# Apollon_ML_testing.net
KiCad netlist of a schematic drawn in EasyEDA
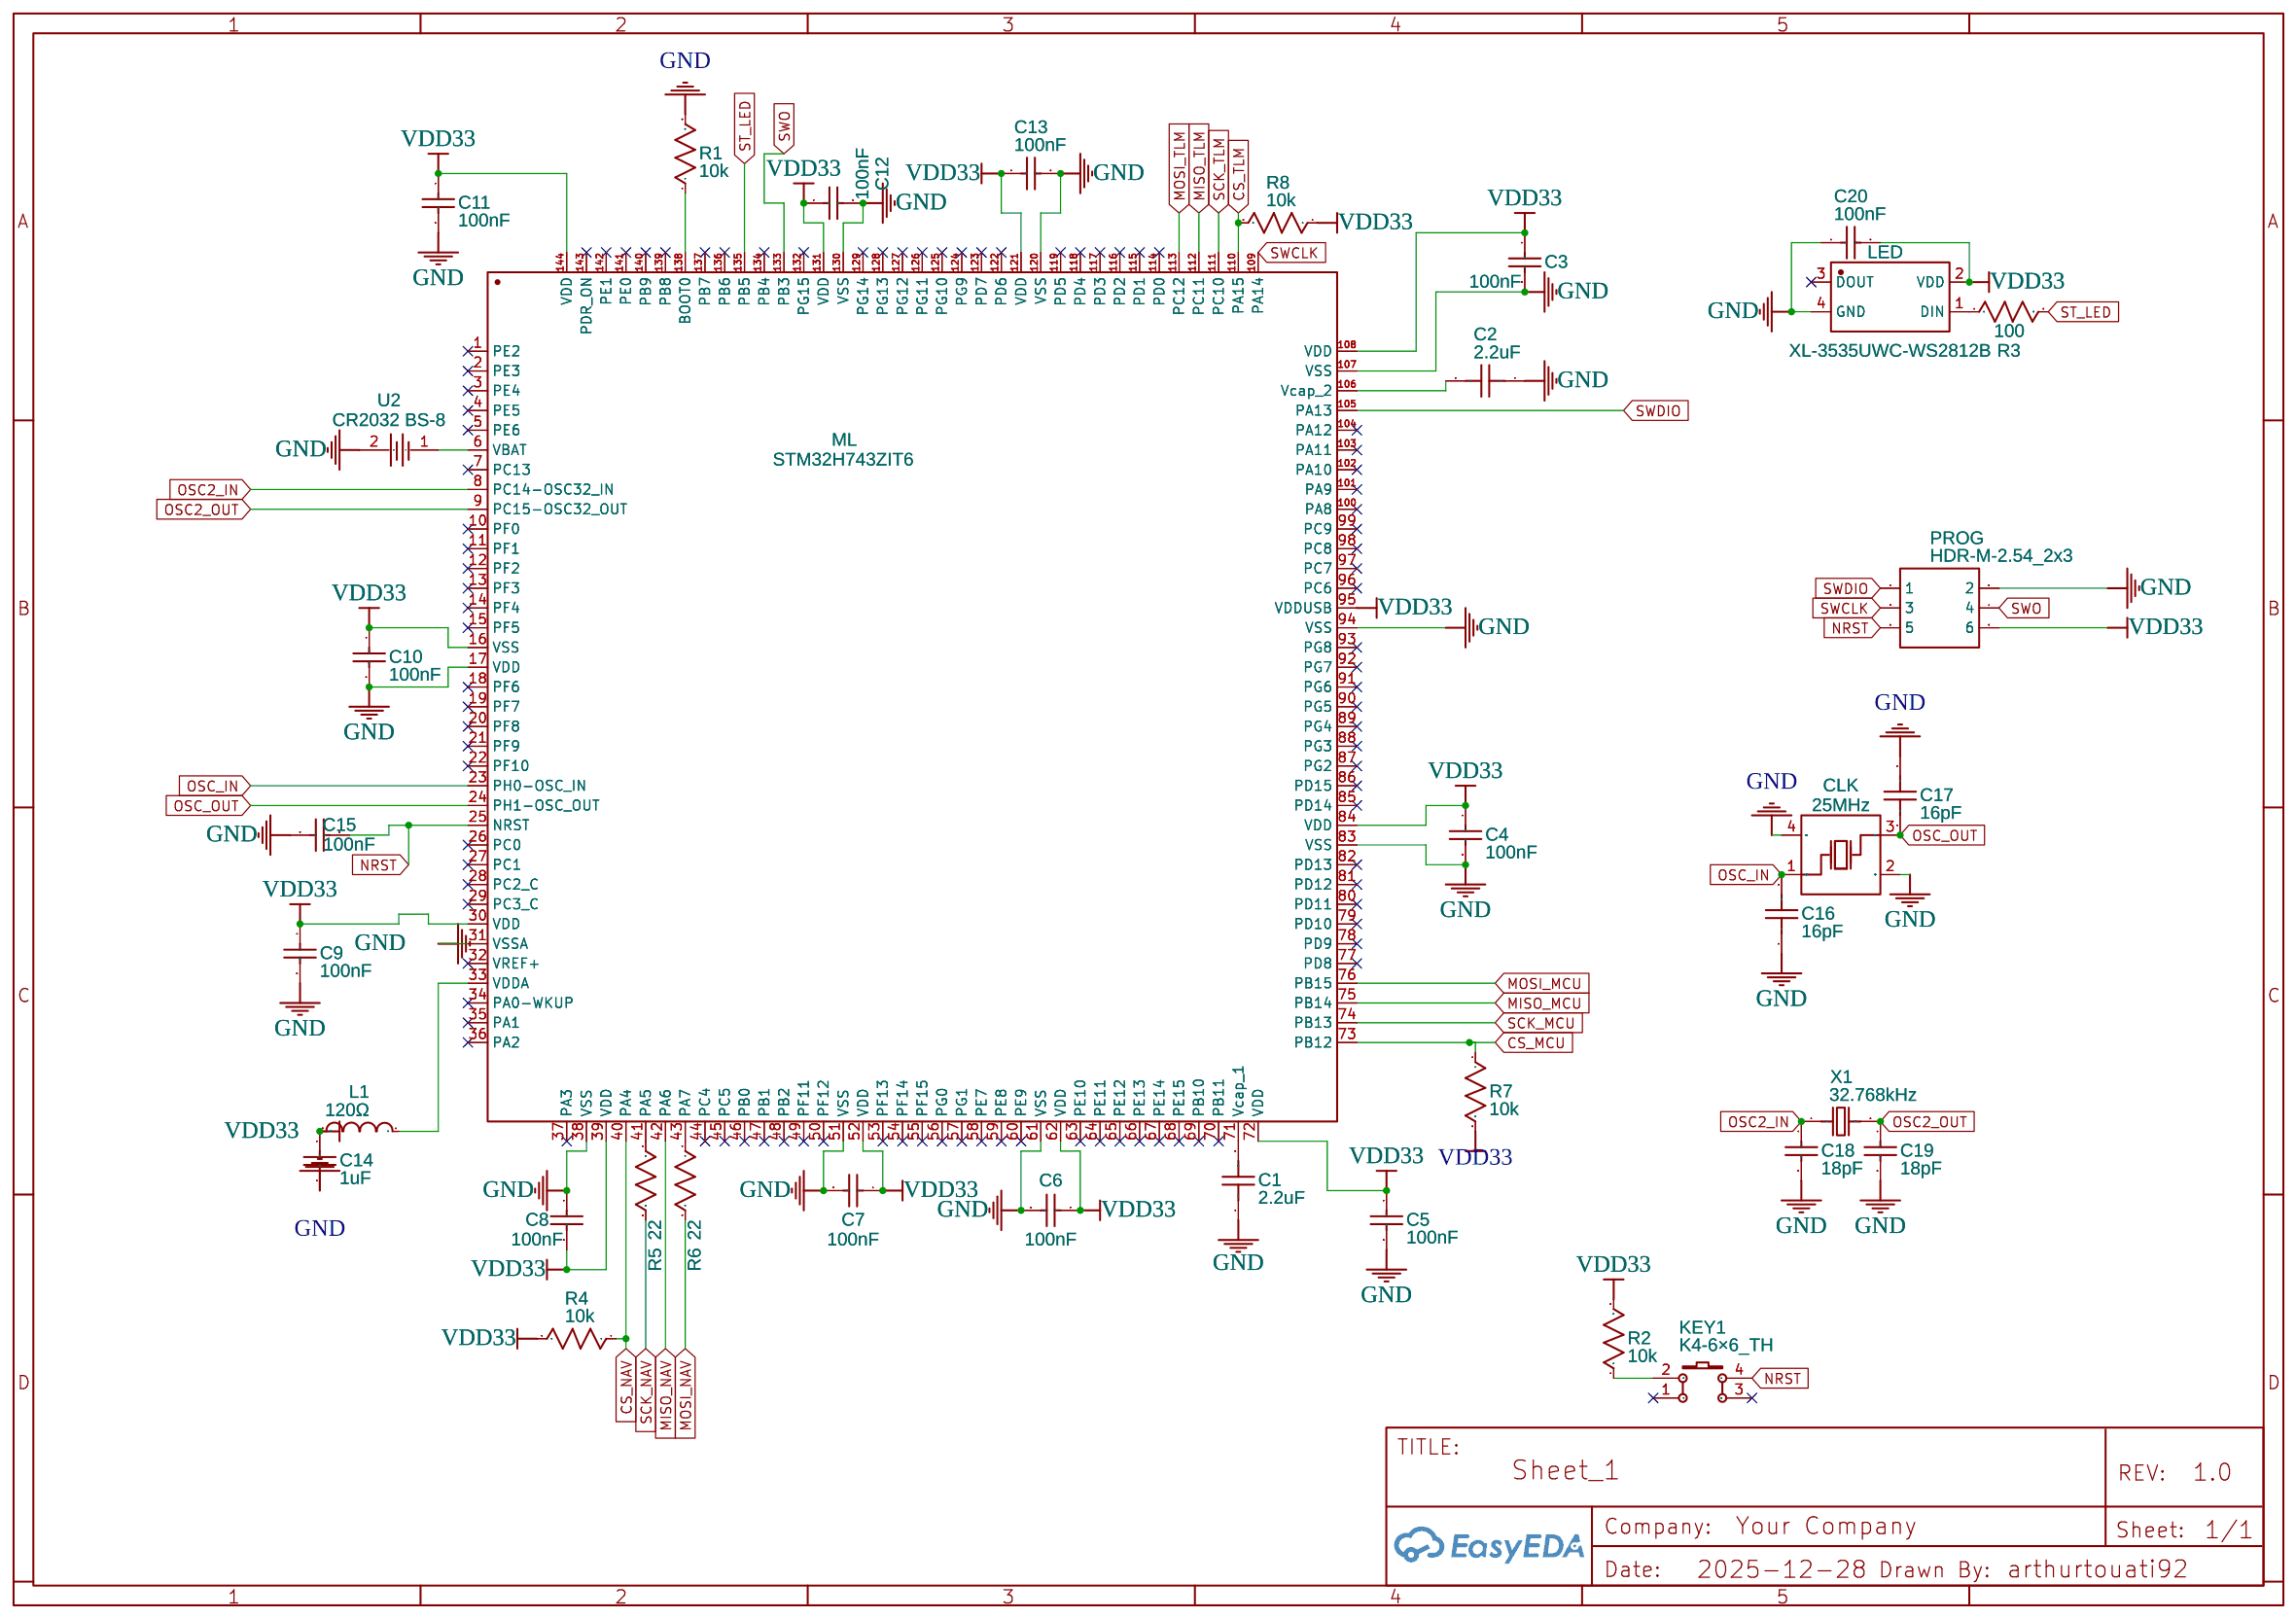
[diagram p0: schematic sheet]

(export (version "E")
  (design (tool "Eeschema 10.0.6"))
  (components
    (comp (ref "C1")
      (value "2.2uF")
      (fields
        (field (name "Manufacturer Part") "CL03A225MP3CRNC")
        (field (name "Manufacturer") "SAMSUNG(三星)")
      )
      (libsource (lib "") (part "CL03A225MP3CRNC_1"))
    )
    (comp (ref "C2")
      (value "2.2uF")
      (fields
        (field (name "Manufacturer Part") "CL03A225MP3CRNC")
        (field (name "Manufacturer") "SAMSUNG(三星)")
      )
      (libsource (lib "") (part "CL03A225MP3CRNC"))
    )
    (comp (ref "C3")
      (value "100nF")
      (fields
        (field (name "Manufacturer Part") "GRM033R61A104KE15D")
        (field (name "Manufacturer") "muRata(村田)")
      )
      (libsource (lib "") (part "GRM033R61A104KE15D"))
    )
    (comp (ref "C4")
      (value "100nF")
      (fields
        (field (name "Manufacturer Part") "GRM033R61A104KE15D")
        (field (name "Manufacturer") "muRata(村田)")
      )
      (libsource (lib "") (part "GRM033R61A104KE15D"))
    )
    (comp (ref "C5")
      (value "100nF")
      (fields
        (field (name "Manufacturer Part") "GRM033R61A104KE15D")
        (field (name "Manufacturer") "muRata(村田)")
      )
      (libsource (lib "") (part "GRM033R61A104KE15D"))
    )
    (comp (ref "C6")
      (value "100nF")
      (fields
        (field (name "Manufacturer Part") "GRM033R61A104KE15D")
        (field (name "Manufacturer") "muRata(村田)")
      )
      (libsource (lib "") (part "GRM033R61A104KE15D_2"))
    )
    (comp (ref "C7")
      (value "100nF")
      (fields
        (field (name "Manufacturer Part") "GRM033R61A104KE15D")
        (field (name "Manufacturer") "muRata(村田)")
      )
      (libsource (lib "") (part "GRM033R61A104KE15D_2"))
    )
    (comp (ref "C8")
      (value "100nF")
      (fields
        (field (name "Manufacturer Part") "GRM033R61A104KE15D")
        (field (name "Manufacturer") "muRata(村田)")
      )
      (libsource (lib "") (part "GRM033R61A104KE15D"))
    )
    (comp (ref "C9")
      (value "100nF")
      (fields
        (field (name "Manufacturer Part") "GRM033R61A104KE15D")
        (field (name "Manufacturer") "muRata(村田)")
      )
      (libsource (lib "") (part "GRM033R61A104KE15D"))
    )
    (comp (ref "C10")
      (value "100nF")
      (fields
        (field (name "Manufacturer Part") "GRM033R61A104KE15D")
        (field (name "Manufacturer") "muRata(村田)")
      )
      (libsource (lib "") (part "GRM033R61A104KE15D"))
    )
    (comp (ref "C11")
      (value "100nF")
      (fields
        (field (name "Manufacturer Part") "GRM033R61A104KE15D")
        (field (name "Manufacturer") "muRata(村田)")
      )
      (libsource (lib "") (part "GRM033R61A104KE15D"))
    )
    (comp (ref "C12")
      (value "100nF")
      (fields
        (field (name "Manufacturer Part") "GRM033R61A104KE15D")
        (field (name "Manufacturer") "muRata(村田)")
      )
      (libsource (lib "") (part "GRM033R61A104KE15D_1"))
    )
    (comp (ref "C13")
      (value "100nF")
      (fields
        (field (name "Manufacturer Part") "GRM033R61A104KE15D")
        (field (name "Manufacturer") "muRata(村田)")
      )
      (libsource (lib "") (part "GRM033R61A104KE15D_1"))
    )
    (comp (ref "C14")
      (value "1uF")
      (fields
        (field (name "Manufacturer Part") "CL03A105MQ3CSNH")
        (field (name "Manufacturer") "SAMSUNG(三星)")
      )
      (libsource (lib "") (part "CL03A105MQ3CSNH"))
    )
    (comp (ref "C15")
      (value "100nF")
      (fields
        (field (name "Manufacturer Part") "GRM033R61A104KE15D")
        (field (name "Manufacturer") "muRata(村田)")
      )
      (libsource (lib "") (part "GRM033R61A104KE15D_2"))
    )
    (comp (ref "C16")
      (value "16pF")
      (fields
        (field (name "Manufacturer Part") "GRM1555C1H160JA01D")
        (field (name "Manufacturer") "muRata(村田)")
      )
      (libsource (lib "") (part "GRM1555C1H160JA01D"))
    )
    (comp (ref "C17")
      (value "16pF")
      (fields
        (field (name "Manufacturer Part") "GRM1555C1H160JA01D")
        (field (name "Manufacturer") "muRata(村田)")
      )
      (libsource (lib "") (part "GRM1555C1H160JA01D"))
    )
    (comp (ref "C18")
      (value "18pF")
      (fields
        (field (name "Manufacturer Part") "GRM033R61A104KE15D")
        (field (name "Manufacturer") "muRata(村田)")
      )
      (libsource (lib "") (part "GRM033R61A104KE15D"))
    )
    (comp (ref "C19")
      (value "18pF")
      (fields
        (field (name "Manufacturer Part") "GRM033R61A104KE15D")
        (field (name "Manufacturer") "muRata(村田)")
      )
      (libsource (lib "") (part "GRM033R61A104KE15D"))
    )
    (comp (ref "C20")
      (value "100nF")
      (fields
        (field (name "Manufacturer Part") "GRM033R61A104KE15D")
        (field (name "Manufacturer") "muRata(村田)")
      )
      (libsource (lib "") (part "GRM033R61A104KE15D_1"))
    )
    (comp (ref "CLK")
      (value "25MHz")
      (fields
        (field (name "Manufacturer Part") "ABM8AIG-25.000MHZ-12-2Z-T3")
        (field (name "Manufacturer") "ABRACON")
      )
      (libsource (lib "") (part "ABM8AIG-25.000MHZ-12-2Z-T3"))
    )
    (comp (ref "KEY1")
      (value "K4-6×6_TH")
      (fields (field (name "Manufacturer Part") "K2-1102DP-E4SW-04") (field (name "Manufacturer") "韩国韩荣"))
      (libsource (lib "") (part "K4-6×6_TH"))
    )
    (comp (ref "L1")
      (value "120Ω")
      (fields (field (name "Manufacturer Part") "BLM03AG121SN1D") (field (name "Manufacturer") "muRata(村田)"))
      (libsource (lib "") (part "BLM03AG121SN1D"))
    )
    (comp (ref "LED")
      (value "XL-3535UWC-WS2812B")
      (fields
        (field (name "Manufacturer Part") "XL-3535UWC-2812B")
        (field (name "Manufacturer") "XINGLIGHT(成兴光)")
      )
      (libsource (lib "") (part "XL-3535UWC-WS2812B"))
    )
    (comp (ref "ML")
      (value "STM32H743ZIT6")
      (fields (field (name "Manufacturer") "ST(意法半导体)"))
      (libsource (lib "") (part "STM32H743ZIT6"))
    )
    (comp (ref "PROG") (value "HDR-M-2.54_2x3") (libsource (lib "") (part "HDR-M-2.54_2x3")))
    (comp (ref "R1") (value "10k") (libsource (lib "") (part "R_0201_US_3")))
    (comp (ref "R2") (value "10k") (libsource (lib "") (part "R_0201_US_3")))
    (comp (ref "R3") (value "100") (libsource (lib "") (part "R_0201_US_1")))
    (comp (ref "R4") (value "10k") (libsource (lib "") (part "R_0201_US_2")))
    (comp (ref "R5") (value "22") (libsource (lib "") (part "R_0201_US")))
    (comp (ref "R6") (value "22") (libsource (lib "") (part "R_0201_US")))
    (comp (ref "R7") (value "10k") (libsource (lib "") (part "R_0201_US")))
    (comp (ref "R8") (value "10k") (libsource (lib "") (part "R_0201_US_2")))
    (comp (ref "U2") (value "CR2032 BS-8") (libsource (lib "") (part "CR2032 BS-8")))
    (comp (ref "X1")
      (value "32.768kHz")
      (fields
        (field (name "Manufacturer Part") "SC-32S32.768kHz20PPM12.5pF")
        (field (name "Manufacturer") "Seiko(精工)")
      )
      (libsource (lib "") (part "SC-32S32.768kHz20PPM12.5pF"))
    )
  )
  (nets
    (net (code "1") (name "CS_MCU") (class "Default")
      (node (ref "ML") (pin "73") (pinfunction "PB12_73") (pintype "unspecified"))
      (node (ref "R7") (pin "1") (pinfunction "1_1") (pintype "unspecified"))
    )
    (net (code "2") (name "CS_NAV") (class "Default")
      (node (ref "ML") (pin "40") (pinfunction "PA4_40") (pintype "unspecified"))
      (node (ref "R4") (pin "1") (pinfunction "1_1") (pintype "unspecified"))
    )
    (net (code "3") (name "CS_TLM") (class "Default")
      (node (ref "ML") (pin "110") (pinfunction "PA15_110") (pintype "unspecified"))
      (node (ref "R8") (pin "2") (pinfunction "2_2") (pintype "unspecified"))
    )
    (net (code "4") (name "GND") (class "Default")
      (node (ref "C1") (pin "1") (pinfunction "1_1") (pintype "unspecified"))
      (node (ref "C10") (pin "2") (pinfunction "2_2") (pintype "input"))
      (node (ref "C11") (pin "2") (pinfunction "2_2") (pintype "input"))
      (node (ref "C12") (pin "2") (pinfunction "2_2") (pintype "input"))
      (node (ref "C13") (pin "2") (pinfunction "2_2") (pintype "input"))
      (node (ref "C14") (pin "2") (pinfunction "2_2") (pintype "input"))
      (node (ref "C15") (pin "2") (pinfunction "2_2") (pintype "input"))
      (node (ref "C16") (pin "1") (pinfunction "1_1") (pintype "unspecified"))
      (node (ref "C17") (pin "2") (pinfunction "2_2") (pintype "unspecified"))
      (node (ref "C18") (pin "2") (pinfunction "2_2") (pintype "input"))
      (node (ref "C19") (pin "2") (pinfunction "2_2") (pintype "input"))
      (node (ref "C2") (pin "1") (pinfunction "1_1") (pintype "unspecified"))
      (node (ref "C20") (pin "1") (pinfunction "1_1") (pintype "input"))
      (node (ref "C3") (pin "2") (pinfunction "2_2") (pintype "input"))
      (node (ref "C4") (pin "2") (pinfunction "2_2") (pintype "input"))
      (node (ref "C5") (pin "2") (pinfunction "2_2") (pintype "input"))
      (node (ref "C6") (pin "2") (pinfunction "2_2") (pintype "input"))
      (node (ref "C7") (pin "2") (pinfunction "2_2") (pintype "input"))
      (node (ref "C8") (pin "1") (pinfunction "1_1") (pintype "input"))
      (node (ref "C9") (pin "2") (pinfunction "2_2") (pintype "input"))
      (node (ref "CLK") (pin "2") (pinfunction "GND_2") (pintype "unspecified"))
      (node (ref "CLK") (pin "4") (pinfunction "GND_4") (pintype "unspecified"))
      (node (ref "LED") (pin "4") (pinfunction "GND_4") (pintype "unspecified"))
      (node (ref "ML") (pin "107") (pinfunction "VSS_107") (pintype "unspecified"))
      (node (ref "ML") (pin "120") (pinfunction "VSS_120") (pintype "unspecified"))
      (node (ref "ML") (pin "130") (pinfunction "VSS_130") (pintype "unspecified"))
      (node (ref "ML") (pin "17") (pinfunction "VDD_17") (pintype "unspecified"))
      (node (ref "ML") (pin "31") (pinfunction "VSSA_31") (pintype "unspecified"))
      (node (ref "ML") (pin "38") (pinfunction "VSS_38") (pintype "unspecified"))
      (node (ref "ML") (pin "51") (pinfunction "VSS_51") (pintype "unspecified"))
      (node (ref "ML") (pin "61") (pinfunction "VSS_61") (pintype "unspecified"))
      (node (ref "ML") (pin "83") (pinfunction "VSS_83") (pintype "unspecified"))
      (node (ref "ML") (pin "94") (pinfunction "VSS_94") (pintype "unspecified"))
      (node (ref "PROG") (pin "2") (pinfunction "2_2") (pintype "input"))
      (node (ref "R1") (pin "2") (pinfunction "2_2") (pintype "unspecified"))
      (node (ref "U2") (pin "2") (pinfunction "+_2") (pintype "input"))
    )
    (net (code "5") (name "MISO_MCU") (class "Default")
      (node (ref "ML") (pin "75") (pinfunction "PB14_75") (pintype "unspecified"))
    )
    (net (code "6") (name "MISO_NAV") (class "Default")
      (node (ref "ML") (pin "42") (pinfunction "PA6_42") (pintype "unspecified"))
    )
    (net (code "7") (name "MISO_TLM") (class "Default")
      (node (ref "ML") (pin "112") (pinfunction "PC11_112") (pintype "unspecified"))
    )
    (net (code "8") (name "MOSI_MCU") (class "Default")
      (node (ref "ML") (pin "76") (pinfunction "PB15_76") (pintype "unspecified"))
    )
    (net (code "9") (name "MOSI_NAV") (class "Default")
      (node (ref "R6") (pin "2") (pinfunction "2_2") (pintype "unspecified"))
    )
    (net (code "10") (name "MOSI_TLM") (class "Default")
      (node (ref "ML") (pin "113") (pinfunction "PC12_113") (pintype "unspecified"))
    )
    (net (code "11") (name "NRST") (class "Default")
      (node (ref "C15") (pin "1") (pinfunction "1_1") (pintype "input"))
      (node (ref "KEY1") (pin "4") (pinfunction "4_4") (pintype "unspecified"))
      (node (ref "ML") (pin "25") (pinfunction "NRST_25") (pintype "unspecified"))
      (node (ref "PROG") (pin "5") (pinfunction "5_5") (pintype "input"))
    )
    (net (code "12") (name "Net-(KEY1-Pad2)") (class "Default")
      (node (ref "KEY1") (pin "2") (pinfunction "2_2") (pintype "unspecified"))
      (node (ref "R2") (pin "1") (pinfunction "1_1") (pintype "unspecified"))
    )
    (net (code "13") (name "Net-(LED-DIN)") (class "Default")
      (node (ref "LED") (pin "1") (pinfunction "DIN_1") (pintype "unspecified"))
      (node (ref "R3") (pin "1") (pinfunction "1_1") (pintype "unspecified"))
    )
    (net (code "14") (name "Net-(ML-BOOT0)") (class "Default")
      (node (ref "ML") (pin "138") (pinfunction "BOOT0_138") (pintype "unspecified"))
      (node (ref "R1") (pin "1") (pinfunction "1_1") (pintype "unspecified"))
    )
    (net (code "15") (name "Net-(ML-PA5)") (class "Default")
      (node (ref "ML") (pin "41") (pinfunction "PA5_41") (pintype "unspecified"))
      (node (ref "R5") (pin "1") (pinfunction "1_1") (pintype "unspecified"))
    )
    (net (code "16") (name "Net-(ML-PA7)") (class "Default")
      (node (ref "ML") (pin "43") (pinfunction "PA7_43") (pintype "unspecified"))
      (node (ref "R6") (pin "1") (pinfunction "1_1") (pintype "unspecified"))
    )
    (net (code "17") (name "Net-(ML-VBAT)") (class "Default")
      (node (ref "ML") (pin "6") (pinfunction "VBAT_6") (pintype "unspecified"))
      (node (ref "U2") (pin "1") (pinfunction "-_1") (pintype "input"))
    )
    (net (code "18") (name "Net-(ML-VDDA)") (class "Default")
      (node (ref "L1") (pin "1") (pinfunction "1_1") (pintype "unspecified"))
      (node (ref "ML") (pin "33") (pinfunction "VDDA_33") (pintype "unspecified"))
    )
    (net (code "19") (name "Net-(ML-Vcap_1)") (class "Default")
      (node (ref "C1") (pin "2") (pinfunction "2_2") (pintype "unspecified"))
      (node (ref "ML") (pin "71") (pinfunction "Vcap_1_71") (pintype "unspecified"))
    )
    (net (code "20") (name "Net-(ML-Vcap_2)") (class "Default")
      (node (ref "C2") (pin "2") (pinfunction "2_2") (pintype "unspecified"))
      (node (ref "ML") (pin "106") (pinfunction "Vcap_2_106") (pintype "unspecified"))
    )
    (net (code "21") (name "OSC2_IN") (class "Default")
      (node (ref "C18") (pin "1") (pinfunction "1_1") (pintype "input"))
      (node (ref "ML") (pin "8") (pinfunction "PC14-OSC32_IN_8") (pintype "unspecified"))
      (node (ref "X1") (pin "1") (pinfunction "1_1") (pintype "unspecified"))
    )
    (net (code "22") (name "OSC2_OUT") (class "Default")
      (node (ref "C19") (pin "1") (pinfunction "1_1") (pintype "input"))
      (node (ref "ML") (pin "9") (pinfunction "PC15-OSC32_OUT_9") (pintype "unspecified"))
      (node (ref "X1") (pin "2") (pinfunction "2_2") (pintype "unspecified"))
    )
    (net (code "23") (name "OSC_IN") (class "Default")
      (node (ref "C16") (pin "2") (pinfunction "2_2") (pintype "unspecified"))
      (node (ref "CLK") (pin "1") (pinfunction "OSC1_1") (pintype "unspecified"))
      (node (ref "ML") (pin "23") (pinfunction "PH0-OSC_IN_23") (pintype "unspecified"))
    )
    (net (code "24") (name "OSC_OUT") (class "Default")
      (node (ref "C17") (pin "1") (pinfunction "1_1") (pintype "unspecified"))
      (node (ref "CLK") (pin "3") (pinfunction "OSC2_3") (pintype "unspecified"))
      (node (ref "ML") (pin "24") (pinfunction "PH1-OSC_OUT_24") (pintype "unspecified"))
    )
    (net (code "25") (name "SCK_MCU") (class "Default")
      (node (ref "ML") (pin "74") (pinfunction "PB13_74") (pintype "unspecified"))
    )
    (net (code "26") (name "SCK_NAV") (class "Default")
      (node (ref "R5") (pin "2") (pinfunction "2_2") (pintype "unspecified"))
    )
    (net (code "27") (name "SCK_TLM") (class "Default")
      (node (ref "ML") (pin "111") (pinfunction "PC10_111") (pintype "unspecified"))
    )
    (net (code "28") (name "ST_LED") (class "Default")
      (node (ref "ML") (pin "135") (pinfunction "PB5_135") (pintype "unspecified"))
      (node (ref "R3") (pin "2") (pinfunction "2_2") (pintype "unspecified"))
    )
    (net (code "29") (name "SWCLK") (class "Default")
      (node (ref "ML") (pin "109") (pinfunction "PA14_109") (pintype "unspecified"))
      (node (ref "PROG") (pin "3") (pinfunction "3_3") (pintype "input"))
    )
    (net (code "30") (name "SWDIO") (class "Default")
      (node (ref "ML") (pin "105") (pinfunction "PA13_105") (pintype "unspecified"))
      (node (ref "PROG") (pin "1") (pinfunction "1_1") (pintype "input"))
    )
    (net (code "31") (name "SWO") (class "Default")
      (node (ref "ML") (pin "133") (pinfunction "PB3_133") (pintype "unspecified"))
      (node (ref "PROG") (pin "4") (pinfunction "4_4") (pintype "input"))
    )
    (net (code "32") (name "VDD33") (class "Default")
      (node (ref "C10") (pin "1") (pinfunction "1_1") (pintype "input"))
      (node (ref "C11") (pin "1") (pinfunction "1_1") (pintype "input"))
      (node (ref "C12") (pin "1") (pinfunction "1_1") (pintype "input"))
      (node (ref "C13") (pin "1") (pinfunction "1_1") (pintype "input"))
      (node (ref "C14") (pin "1") (pinfunction "1_1") (pintype "input"))
      (node (ref "C20") (pin "2") (pinfunction "2_2") (pintype "input"))
      (node (ref "C3") (pin "1") (pinfunction "1_1") (pintype "input"))
      (node (ref "C4") (pin "1") (pinfunction "1_1") (pintype "input"))
      (node (ref "C5") (pin "1") (pinfunction "1_1") (pintype "input"))
      (node (ref "C6") (pin "1") (pinfunction "1_1") (pintype "input"))
      (node (ref "C7") (pin "1") (pinfunction "1_1") (pintype "input"))
      (node (ref "C8") (pin "2") (pinfunction "2_2") (pintype "input"))
      (node (ref "C9") (pin "1") (pinfunction "1_1") (pintype "input"))
      (node (ref "L1") (pin "2") (pinfunction "2_2") (pintype "unspecified"))
      (node (ref "LED") (pin "2") (pinfunction "VDD_2") (pintype "unspecified"))
      (node (ref "ML") (pin "108") (pinfunction "VDD_108") (pintype "unspecified"))
      (node (ref "ML") (pin "121") (pinfunction "VDD_121") (pintype "unspecified"))
      (node (ref "ML") (pin "131") (pinfunction "VDD_131") (pintype "unspecified"))
      (node (ref "ML") (pin "144") (pinfunction "VDD_144") (pintype "unspecified"))
      (node (ref "ML") (pin "16") (pinfunction "VSS_16") (pintype "unspecified"))
      (node (ref "ML") (pin "30") (pinfunction "VDD_30") (pintype "unspecified"))
      (node (ref "ML") (pin "39") (pinfunction "VDD_39") (pintype "unspecified"))
      (node (ref "ML") (pin "52") (pinfunction "VDD_52") (pintype "unspecified"))
      (node (ref "ML") (pin "62") (pinfunction "VDD_62") (pintype "unspecified"))
      (node (ref "ML") (pin "72") (pinfunction "VDD_72") (pintype "unspecified"))
      (node (ref "ML") (pin "84") (pinfunction "VDD_84") (pintype "unspecified"))
      (node (ref "ML") (pin "95") (pinfunction "VDDUSB_95") (pintype "unspecified"))
      (node (ref "PROG") (pin "6") (pinfunction "6_6") (pintype "input"))
      (node (ref "R2") (pin "2") (pinfunction "2_2") (pintype "unspecified"))
      (node (ref "R4") (pin "2") (pinfunction "2_2") (pintype "unspecified"))
      (node (ref "R7") (pin "2") (pinfunction "2_2") (pintype "unspecified"))
      (node (ref "R8") (pin "1") (pinfunction "1_1") (pintype "unspecified"))
    )
    (net (code "33") (name "unconnected-(KEY1-Pad1)") (class "Default")
      (node (ref "KEY1") (pin "1") (pinfunction "1_1") (pintype "unspecified+no_connect"))
    )
    (net (code "34") (name "unconnected-(KEY1-Pad3)") (class "Default")
      (node (ref "KEY1") (pin "3") (pinfunction "3_3") (pintype "unspecified+no_connect"))
    )
    (net (code "35") (name "unconnected-(LED-DOUT-Pad3)") (class "Default")
      (node (ref "LED") (pin "3") (pinfunction "DOUT_3") (pintype "unspecified+no_connect"))
    )
    (net (code "36") (name "unconnected-(ML-PA0-WKUP-Pad34)") (class "Default")
      (node (ref "ML") (pin "34") (pinfunction "PA0-WKUP_34") (pintype "unspecified+no_connect"))
    )
    (net (code "37") (name "unconnected-(ML-PA1-Pad35)") (class "Default")
      (node (ref "ML") (pin "35") (pinfunction "PA1_35") (pintype "unspecified+no_connect"))
    )
    (net (code "38") (name "unconnected-(ML-PA2-Pad36)") (class "Default")
      (node (ref "ML") (pin "36") (pinfunction "PA2_36") (pintype "unspecified+no_connect"))
    )
    (net (code "39") (name "unconnected-(ML-PA3-Pad37)") (class "Default")
      (node (ref "ML") (pin "37") (pinfunction "PA3_37") (pintype "unspecified+no_connect"))
    )
    (net (code "40") (name "unconnected-(ML-PA8-Pad100)") (class "Default")
      (node (ref "ML") (pin "100") (pinfunction "PA8_100") (pintype "unspecified+no_connect"))
    )
    (net (code "41") (name "unconnected-(ML-PA9-Pad101)") (class "Default")
      (node (ref "ML") (pin "101") (pinfunction "PA9_101") (pintype "unspecified+no_connect"))
    )
    (net (code "42") (name "unconnected-(ML-PA10-Pad102)") (class "Default")
      (node (ref "ML") (pin "102") (pinfunction "PA10_102") (pintype "unspecified+no_connect"))
    )
    (net (code "43") (name "unconnected-(ML-PA11-Pad103)") (class "Default")
      (node (ref "ML") (pin "103") (pinfunction "PA11_103") (pintype "unspecified+no_connect"))
    )
    (net (code "44") (name "unconnected-(ML-PA12-Pad104)") (class "Default")
      (node (ref "ML") (pin "104") (pinfunction "PA12_104") (pintype "unspecified+no_connect"))
    )
    (net (code "45") (name "unconnected-(ML-PB0-Pad46)") (class "Default")
      (node (ref "ML") (pin "46") (pinfunction "PB0_46") (pintype "unspecified+no_connect"))
    )
    (net (code "46") (name "unconnected-(ML-PB1-Pad47)") (class "Default")
      (node (ref "ML") (pin "47") (pinfunction "PB1_47") (pintype "unspecified+no_connect"))
    )
    (net (code "47") (name "unconnected-(ML-PB2-Pad48)") (class "Default")
      (node (ref "ML") (pin "48") (pinfunction "PB2_48") (pintype "unspecified+no_connect"))
    )
    (net (code "48") (name "unconnected-(ML-PB4-Pad134)") (class "Default")
      (node (ref "ML") (pin "134") (pinfunction "PB4_134") (pintype "unspecified+no_connect"))
    )
    (net (code "49") (name "unconnected-(ML-PB6-Pad136)") (class "Default")
      (node (ref "ML") (pin "136") (pinfunction "PB6_136") (pintype "unspecified+no_connect"))
    )
    (net (code "50") (name "unconnected-(ML-PB7-Pad137)") (class "Default")
      (node (ref "ML") (pin "137") (pinfunction "PB7_137") (pintype "unspecified+no_connect"))
    )
    (net (code "51") (name "unconnected-(ML-PB8-Pad139)") (class "Default")
      (node (ref "ML") (pin "139") (pinfunction "PB8_139") (pintype "unspecified+no_connect"))
    )
    (net (code "52") (name "unconnected-(ML-PB9-Pad140)") (class "Default")
      (node (ref "ML") (pin "140") (pinfunction "PB9_140") (pintype "unspecified+no_connect"))
    )
    (net (code "53") (name "unconnected-(ML-PB10-Pad69)") (class "Default")
      (node (ref "ML") (pin "69") (pinfunction "PB10_69") (pintype "unspecified+no_connect"))
    )
    (net (code "54") (name "unconnected-(ML-PB11-Pad70)") (class "Default")
      (node (ref "ML") (pin "70") (pinfunction "PB11_70") (pintype "unspecified+no_connect"))
    )
    (net (code "55") (name "unconnected-(ML-PC0-Pad26)") (class "Default")
      (node (ref "ML") (pin "26") (pinfunction "PC0_26") (pintype "unspecified+no_connect"))
    )
    (net (code "56") (name "unconnected-(ML-PC1-Pad27)") (class "Default")
      (node (ref "ML") (pin "27") (pinfunction "PC1_27") (pintype "unspecified+no_connect"))
    )
    (net (code "57") (name "unconnected-(ML-PC2_C-Pad28)") (class "Default")
      (node (ref "ML") (pin "28") (pinfunction "PC2_C_28") (pintype "unspecified+no_connect"))
    )
    (net (code "58") (name "unconnected-(ML-PC3_C-Pad29)") (class "Default")
      (node (ref "ML") (pin "29") (pinfunction "PC3_C_29") (pintype "unspecified+no_connect"))
    )
    (net (code "59") (name "unconnected-(ML-PC4-Pad44)") (class "Default")
      (node (ref "ML") (pin "44") (pinfunction "PC4_44") (pintype "unspecified+no_connect"))
    )
    (net (code "60") (name "unconnected-(ML-PC5-Pad45)") (class "Default")
      (node (ref "ML") (pin "45") (pinfunction "PC5_45") (pintype "unspecified+no_connect"))
    )
    (net (code "61") (name "unconnected-(ML-PC6-Pad96)") (class "Default")
      (node (ref "ML") (pin "96") (pinfunction "PC6_96") (pintype "unspecified+no_connect"))
    )
    (net (code "62") (name "unconnected-(ML-PC7-Pad97)") (class "Default")
      (node (ref "ML") (pin "97") (pinfunction "PC7_97") (pintype "unspecified+no_connect"))
    )
    (net (code "63") (name "unconnected-(ML-PC8-Pad98)") (class "Default")
      (node (ref "ML") (pin "98") (pinfunction "PC8_98") (pintype "unspecified+no_connect"))
    )
    (net (code "64") (name "unconnected-(ML-PC9-Pad99)") (class "Default")
      (node (ref "ML") (pin "99") (pinfunction "PC9_99") (pintype "unspecified+no_connect"))
    )
    (net (code "65") (name "unconnected-(ML-PC13-Pad7)") (class "Default")
      (node (ref "ML") (pin "7") (pinfunction "PC13_7") (pintype "unspecified+no_connect"))
    )
    (net (code "66") (name "unconnected-(ML-PD0-Pad114)") (class "Default")
      (node (ref "ML") (pin "114") (pinfunction "PD0_114") (pintype "unspecified+no_connect"))
    )
    (net (code "67") (name "unconnected-(ML-PD1-Pad115)") (class "Default")
      (node (ref "ML") (pin "115") (pinfunction "PD1_115") (pintype "unspecified+no_connect"))
    )
    (net (code "68") (name "unconnected-(ML-PD2-Pad116)") (class "Default")
      (node (ref "ML") (pin "116") (pinfunction "PD2_116") (pintype "unspecified+no_connect"))
    )
    (net (code "69") (name "unconnected-(ML-PD3-Pad117)") (class "Default")
      (node (ref "ML") (pin "117") (pinfunction "PD3_117") (pintype "unspecified+no_connect"))
    )
    (net (code "70") (name "unconnected-(ML-PD4-Pad118)") (class "Default")
      (node (ref "ML") (pin "118") (pinfunction "PD4_118") (pintype "unspecified+no_connect"))
    )
    (net (code "71") (name "unconnected-(ML-PD5-Pad119)") (class "Default")
      (node (ref "ML") (pin "119") (pinfunction "PD5_119") (pintype "unspecified+no_connect"))
    )
    (net (code "72") (name "unconnected-(ML-PD6-Pad122)") (class "Default")
      (node (ref "ML") (pin "122") (pinfunction "PD6_122") (pintype "unspecified+no_connect"))
    )
    (net (code "73") (name "unconnected-(ML-PD7-Pad123)") (class "Default")
      (node (ref "ML") (pin "123") (pinfunction "PD7_123") (pintype "unspecified+no_connect"))
    )
    (net (code "74") (name "unconnected-(ML-PD8-Pad77)") (class "Default")
      (node (ref "ML") (pin "77") (pinfunction "PD8_77") (pintype "unspecified+no_connect"))
    )
    (net (code "75") (name "unconnected-(ML-PD9-Pad78)") (class "Default")
      (node (ref "ML") (pin "78") (pinfunction "PD9_78") (pintype "unspecified+no_connect"))
    )
    (net (code "76") (name "unconnected-(ML-PD10-Pad79)") (class "Default")
      (node (ref "ML") (pin "79") (pinfunction "PD10_79") (pintype "unspecified+no_connect"))
    )
    (net (code "77") (name "unconnected-(ML-PD11-Pad80)") (class "Default")
      (node (ref "ML") (pin "80") (pinfunction "PD11_80") (pintype "unspecified+no_connect"))
    )
    (net (code "78") (name "unconnected-(ML-PD12-Pad81)") (class "Default")
      (node (ref "ML") (pin "81") (pinfunction "PD12_81") (pintype "unspecified+no_connect"))
    )
    (net (code "79") (name "unconnected-(ML-PD13-Pad82)") (class "Default")
      (node (ref "ML") (pin "82") (pinfunction "PD13_82") (pintype "unspecified+no_connect"))
    )
    (net (code "80") (name "unconnected-(ML-PD14-Pad85)") (class "Default")
      (node (ref "ML") (pin "85") (pinfunction "PD14_85") (pintype "unspecified+no_connect"))
    )
    (net (code "81") (name "unconnected-(ML-PD15-Pad86)") (class "Default")
      (node (ref "ML") (pin "86") (pinfunction "PD15_86") (pintype "unspecified+no_connect"))
    )
    (net (code "82") (name "unconnected-(ML-PDR_ON-Pad143)") (class "Default")
      (node (ref "ML") (pin "143") (pinfunction "PDR_ON_143") (pintype "unspecified+no_connect"))
    )
    (net (code "83") (name "unconnected-(ML-PE0-Pad141)") (class "Default")
      (node (ref "ML") (pin "141") (pinfunction "PE0_141") (pintype "unspecified+no_connect"))
    )
    (net (code "84") (name "unconnected-(ML-PE1-Pad142)") (class "Default")
      (node (ref "ML") (pin "142") (pinfunction "PE1_142") (pintype "unspecified+no_connect"))
    )
    (net (code "85") (name "unconnected-(ML-PE2-Pad1)") (class "Default")
      (node (ref "ML") (pin "1") (pinfunction "PE2_1") (pintype "unspecified+no_connect"))
    )
    (net (code "86") (name "unconnected-(ML-PE3-Pad2)") (class "Default")
      (node (ref "ML") (pin "2") (pinfunction "PE3_2") (pintype "unspecified+no_connect"))
    )
    (net (code "87") (name "unconnected-(ML-PE4-Pad3)") (class "Default")
      (node (ref "ML") (pin "3") (pinfunction "PE4_3") (pintype "unspecified+no_connect"))
    )
    (net (code "88") (name "unconnected-(ML-PE5-Pad4)") (class "Default")
      (node (ref "ML") (pin "4") (pinfunction "PE5_4") (pintype "unspecified+no_connect"))
    )
    (net (code "89") (name "unconnected-(ML-PE6-Pad5)") (class "Default")
      (node (ref "ML") (pin "5") (pinfunction "PE6_5") (pintype "unspecified+no_connect"))
    )
    (net (code "90") (name "unconnected-(ML-PE7-Pad58)") (class "Default")
      (node (ref "ML") (pin "58") (pinfunction "PE7_58") (pintype "unspecified+no_connect"))
    )
    (net (code "91") (name "unconnected-(ML-PE8-Pad59)") (class "Default")
      (node (ref "ML") (pin "59") (pinfunction "PE8_59") (pintype "unspecified+no_connect"))
    )
    (net (code "92") (name "unconnected-(ML-PE9-Pad60)") (class "Default")
      (node (ref "ML") (pin "60") (pinfunction "PE9_60") (pintype "unspecified+no_connect"))
    )
    (net (code "93") (name "unconnected-(ML-PE10-Pad63)") (class "Default")
      (node (ref "ML") (pin "63") (pinfunction "PE10_63") (pintype "unspecified+no_connect"))
    )
    (net (code "94") (name "unconnected-(ML-PE11-Pad64)") (class "Default")
      (node (ref "ML") (pin "64") (pinfunction "PE11_64") (pintype "unspecified+no_connect"))
    )
    (net (code "95") (name "unconnected-(ML-PE12-Pad65)") (class "Default")
      (node (ref "ML") (pin "65") (pinfunction "PE12_65") (pintype "unspecified+no_connect"))
    )
    (net (code "96") (name "unconnected-(ML-PE13-Pad66)") (class "Default")
      (node (ref "ML") (pin "66") (pinfunction "PE13_66") (pintype "unspecified+no_connect"))
    )
    (net (code "97") (name "unconnected-(ML-PE14-Pad67)") (class "Default")
      (node (ref "ML") (pin "67") (pinfunction "PE14_67") (pintype "unspecified+no_connect"))
    )
    (net (code "98") (name "unconnected-(ML-PE15-Pad68)") (class "Default")
      (node (ref "ML") (pin "68") (pinfunction "PE15_68") (pintype "unspecified+no_connect"))
    )
    (net (code "99") (name "unconnected-(ML-PF0-Pad10)") (class "Default")
      (node (ref "ML") (pin "10") (pinfunction "PF0_10") (pintype "unspecified+no_connect"))
    )
    (net (code "100") (name "unconnected-(ML-PF1-Pad11)") (class "Default")
      (node (ref "ML") (pin "11") (pinfunction "PF1_11") (pintype "unspecified+no_connect"))
    )
    (net (code "101") (name "unconnected-(ML-PF2-Pad12)") (class "Default")
      (node (ref "ML") (pin "12") (pinfunction "PF2_12") (pintype "unspecified+no_connect"))
    )
    (net (code "102") (name "unconnected-(ML-PF3-Pad13)") (class "Default")
      (node (ref "ML") (pin "13") (pinfunction "PF3_13") (pintype "unspecified+no_connect"))
    )
    (net (code "103") (name "unconnected-(ML-PF4-Pad14)") (class "Default")
      (node (ref "ML") (pin "14") (pinfunction "PF4_14") (pintype "unspecified+no_connect"))
    )
    (net (code "104") (name "unconnected-(ML-PF5-Pad15)") (class "Default")
      (node (ref "ML") (pin "15") (pinfunction "PF5_15") (pintype "unspecified+no_connect"))
    )
    (net (code "105") (name "unconnected-(ML-PF6-Pad18)") (class "Default")
      (node (ref "ML") (pin "18") (pinfunction "PF6_18") (pintype "unspecified+no_connect"))
    )
    (net (code "106") (name "unconnected-(ML-PF7-Pad19)") (class "Default")
      (node (ref "ML") (pin "19") (pinfunction "PF7_19") (pintype "unspecified+no_connect"))
    )
    (net (code "107") (name "unconnected-(ML-PF8-Pad20)") (class "Default")
      (node (ref "ML") (pin "20") (pinfunction "PF8_20") (pintype "unspecified+no_connect"))
    )
    (net (code "108") (name "unconnected-(ML-PF9-Pad21)") (class "Default")
      (node (ref "ML") (pin "21") (pinfunction "PF9_21") (pintype "unspecified+no_connect"))
    )
    (net (code "109") (name "unconnected-(ML-PF10-Pad22)") (class "Default")
      (node (ref "ML") (pin "22") (pinfunction "PF10_22") (pintype "unspecified+no_connect"))
    )
    (net (code "110") (name "unconnected-(ML-PF11-Pad49)") (class "Default")
      (node (ref "ML") (pin "49") (pinfunction "PF11_49") (pintype "unspecified+no_connect"))
    )
    (net (code "111") (name "unconnected-(ML-PF12-Pad50)") (class "Default")
      (node (ref "ML") (pin "50") (pinfunction "PF12_50") (pintype "unspecified+no_connect"))
    )
    (net (code "112") (name "unconnected-(ML-PF13-Pad53)") (class "Default")
      (node (ref "ML") (pin "53") (pinfunction "PF13_53") (pintype "unspecified+no_connect"))
    )
    (net (code "113") (name "unconnected-(ML-PF14-Pad54)") (class "Default")
      (node (ref "ML") (pin "54") (pinfunction "PF14_54") (pintype "unspecified+no_connect"))
    )
    (net (code "114") (name "unconnected-(ML-PF15-Pad55)") (class "Default")
      (node (ref "ML") (pin "55") (pinfunction "PF15_55") (pintype "unspecified+no_connect"))
    )
    (net (code "115") (name "unconnected-(ML-PG0-Pad56)") (class "Default")
      (node (ref "ML") (pin "56") (pinfunction "PG0_56") (pintype "unspecified+no_connect"))
    )
    (net (code "116") (name "unconnected-(ML-PG1-Pad57)") (class "Default")
      (node (ref "ML") (pin "57") (pinfunction "PG1_57") (pintype "unspecified+no_connect"))
    )
    (net (code "117") (name "unconnected-(ML-PG2-Pad87)") (class "Default")
      (node (ref "ML") (pin "87") (pinfunction "PG2_87") (pintype "unspecified+no_connect"))
    )
    (net (code "118") (name "unconnected-(ML-PG3-Pad88)") (class "Default")
      (node (ref "ML") (pin "88") (pinfunction "PG3_88") (pintype "unspecified+no_connect"))
    )
    (net (code "119") (name "unconnected-(ML-PG4-Pad89)") (class "Default")
      (node (ref "ML") (pin "89") (pinfunction "PG4_89") (pintype "unspecified+no_connect"))
    )
    (net (code "120") (name "unconnected-(ML-PG5-Pad90)") (class "Default")
      (node (ref "ML") (pin "90") (pinfunction "PG5_90") (pintype "unspecified+no_connect"))
    )
    (net (code "121") (name "unconnected-(ML-PG6-Pad91)") (class "Default")
      (node (ref "ML") (pin "91") (pinfunction "PG6_91") (pintype "unspecified+no_connect"))
    )
    (net (code "122") (name "unconnected-(ML-PG7-Pad92)") (class "Default")
      (node (ref "ML") (pin "92") (pinfunction "PG7_92") (pintype "unspecified+no_connect"))
    )
    (net (code "123") (name "unconnected-(ML-PG8-Pad93)") (class "Default")
      (node (ref "ML") (pin "93") (pinfunction "PG8_93") (pintype "unspecified+no_connect"))
    )
    (net (code "124") (name "unconnected-(ML-PG9-Pad124)") (class "Default")
      (node (ref "ML") (pin "124") (pinfunction "PG9_124") (pintype "unspecified+no_connect"))
    )
    (net (code "125") (name "unconnected-(ML-PG10-Pad125)") (class "Default")
      (node (ref "ML") (pin "125") (pinfunction "PG10_125") (pintype "unspecified+no_connect"))
    )
    (net (code "126") (name "unconnected-(ML-PG11-Pad126)") (class "Default")
      (node (ref "ML") (pin "126") (pinfunction "PG11_126") (pintype "unspecified+no_connect"))
    )
    (net (code "127") (name "unconnected-(ML-PG12-Pad127)") (class "Default")
      (node (ref "ML") (pin "127") (pinfunction "PG12_127") (pintype "unspecified+no_connect"))
    )
    (net (code "128") (name "unconnected-(ML-PG13-Pad128)") (class "Default")
      (node (ref "ML") (pin "128") (pinfunction "PG13_128") (pintype "unspecified+no_connect"))
    )
    (net (code "129") (name "unconnected-(ML-PG14-Pad129)") (class "Default")
      (node (ref "ML") (pin "129") (pinfunction "PG14_129") (pintype "unspecified+no_connect"))
    )
    (net (code "130") (name "unconnected-(ML-PG15-Pad132)") (class "Default")
      (node (ref "ML") (pin "132") (pinfunction "PG15_132") (pintype "unspecified+no_connect"))
    )
    (net (code "131") (name "unconnected-(ML-VREF+-Pad32)") (class "Default")
      (node (ref "ML") (pin "32") (pinfunction "VREF+_32") (pintype "unspecified+no_connect"))
    )
  )
)
